# FiringBoard.net
KiCad netlist of a schematic drawn in Altium Designer
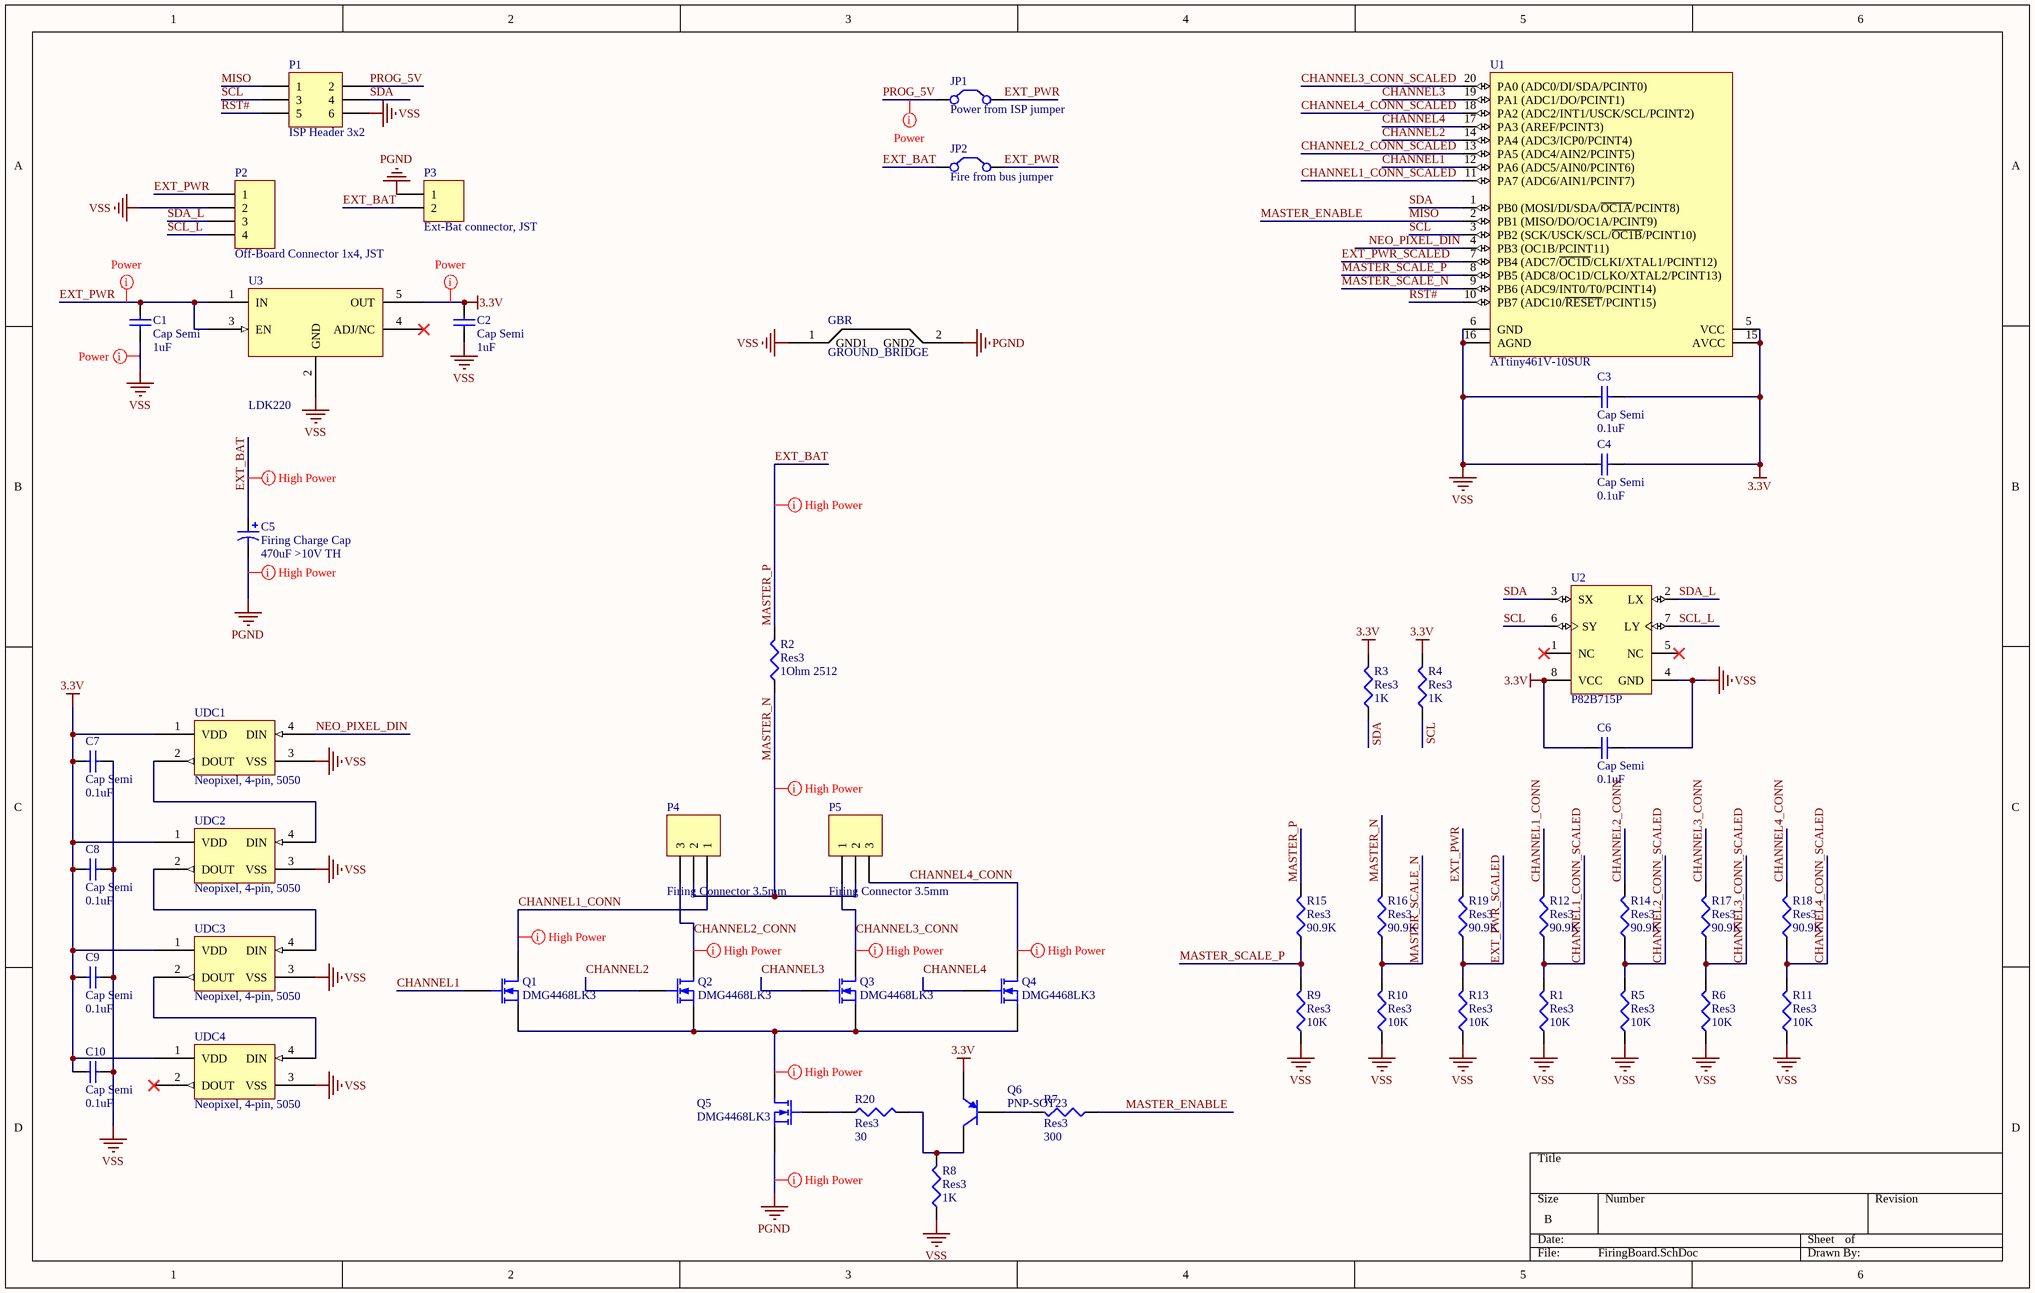
[diagram p0: FiringBoard.SchDoc]

(export (version "E")
  (design (tool "Eeschema 10.0.6"))
  (components
    (comp (ref "C1")
      (value "Cap Semi")
      (footprint "C0603")
      (description "Capacitor (Semiconductor SIM Model)")
      (fields (field (name "ALTIUM_VALUE") "1uF") (field (name "PUBLISHER") "Altium Limited"))
      (libsource (lib "Miscellaneous Devices") (part "Cap Semi"))
    )
    (comp (ref "C2")
      (value "Cap Semi")
      (footprint "C0603")
      (description "Capacitor (Semiconductor SIM Model)")
      (fields (field (name "ALTIUM_VALUE") "1uF") (field (name "PUBLISHER") "Altium Limited"))
      (libsource (lib "Miscellaneous Devices") (part "Cap Semi"))
    )
    (comp (ref "C3")
      (value "Cap Semi")
      (footprint "C0603")
      (description "Capacitor (Semiconductor SIM Model)")
      (fields (field (name "ALTIUM_VALUE") "0.1uF") (field (name "PUBLISHER") "Altium Limited"))
      (libsource (lib "Miscellaneous Devices") (part "Cap Semi"))
    )
    (comp (ref "C4")
      (value "Cap Semi")
      (footprint "C0603")
      (description "Capacitor (Semiconductor SIM Model)")
      (fields (field (name "ALTIUM_VALUE") "0.1uF") (field (name "PUBLISHER") "Altium Limited"))
      (libsource (lib "Miscellaneous Devices") (part "Cap Semi"))
    )
    (comp (ref "C5")
      (value "Firing Charge Cap")
      (footprint "CAPPR-10x12.5-Flat-Right")
      (description "Polarized Capacitor (Radial)")
      (fields (field (name "ALTIUM_VALUE") "470uF >10V TH") (field (name "PUBLISHER") "Altium Limited"))
      (libsource (lib "Miscellaneous Devices") (part "Cap Pol1"))
    )
    (comp (ref "C6")
      (value "Cap Semi")
      (footprint "C0603")
      (description "Capacitor (Semiconductor SIM Model)")
      (fields (field (name "ALTIUM_VALUE") "0.1uF") (field (name "PUBLISHER") "Altium Limited"))
      (libsource (lib "Miscellaneous Devices") (part "Cap Semi"))
    )
    (comp (ref "C7")
      (value "Cap Semi")
      (footprint "C0603")
      (description "Capacitor (Semiconductor SIM Model)")
      (fields (field (name "ALTIUM_VALUE") "0.1uF") (field (name "PUBLISHER") "Altium Limited"))
      (libsource (lib "Miscellaneous Devices") (part "Cap Semi"))
    )
    (comp (ref "C8")
      (value "Cap Semi")
      (footprint "C0603")
      (description "Capacitor (Semiconductor SIM Model)")
      (fields (field (name "ALTIUM_VALUE") "0.1uF") (field (name "PUBLISHER") "Altium Limited"))
      (libsource (lib "Miscellaneous Devices") (part "Cap Semi"))
    )
    (comp (ref "C9")
      (value "Cap Semi")
      (footprint "C0603")
      (description "Capacitor (Semiconductor SIM Model)")
      (fields (field (name "ALTIUM_VALUE") "0.1uF") (field (name "PUBLISHER") "Altium Limited"))
      (libsource (lib "Miscellaneous Devices") (part "Cap Semi"))
    )
    (comp (ref "C10")
      (value "Cap Semi")
      (footprint "C0603")
      (description "Capacitor (Semiconductor SIM Model)")
      (fields (field (name "ALTIUM_VALUE") "0.1uF") (field (name "PUBLISHER") "Altium Limited"))
      (libsource (lib "Miscellaneous Devices") (part "Cap Semi"))
    )
    (comp (ref "GBR")
      (value "GROUND_BRIDGE")
      (footprint "GROUND_BRIDGE")
      (libsource (lib "Schlib1") (part "GROUND_BRIDGE"))
    )
    (comp (ref "JP1")
      (value "Power from ISP jumper")
      (footprint "SOLDER-JUMPER-3D")
      (description "Solder Configuration Jumper")
      (fields (field (name "PUBLISHER") "Altium Limited"))
      (libsource (lib "SolarCar") (part "SolderJumper"))
    )
    (comp (ref "JP2")
      (value "Fire from bus jumper")
      (footprint "SOLDER-JUMPER-3D")
      (description "Solder Configuration Jumper")
      (fields (field (name "PUBLISHER") "Altium Limited"))
      (libsource (lib "SolarCar") (part "SolderJumper"))
    )
    (comp (ref "P1")
      (value "ISP Header 3x2")
      (footprint "HDR2X3-AVRISP")
      (description "Header, 3-Pin, Dual row")
      (fields (field (name "PUBLISHER") "Altium Limited"))
      (libsource (lib "Miscellaneous Connectors") (part "Header 3X2"))
    )
    (comp (ref "P2")
      (value "Off-Board Connector 1x4, JST")
      (footprint "1x04-1.5MM-JST")
      (description "Header, 4-Pin")
      (fields (field (name "PUBLISHER") "Altium Limited"))
      (libsource (lib "Miscellaneous Connectors") (part "Header 4"))
    )
    (comp (ref "P3")
      (value "Ext-Bat connector, JST")
      (footprint "JST-2-PTH-NS")
      (description "Header, 2-Pin")
      (fields (field (name "PUBLISHER") "Altium Limited"))
      (libsource (lib "Miscellaneous Connectors") (part "Header 2"))
    )
    (comp (ref "P4")
      (value "Firing Connector 3.5mm")
      (footprint "20020327-C031B01LF")
      (description "Header, 3-Pin")
      (fields (field (name "PUBLISHER") "Altium Limited"))
      (libsource (lib "") (part "Header 3_1"))
    )
    (comp (ref "P5")
      (value "Firing Connector 3.5mm")
      (footprint "20020327-C031B01LF")
      (description "Header, 3-Pin")
      (fields (field (name "PUBLISHER") "Altium Limited"))
      (libsource (lib "Miscellaneous Connectors") (part "Header 3"))
    )
    (comp (ref "Q1")
      (value "DMG4468LK3")
      (footprint "TO252")
      (description "N-CHANNEL ENHANCEMENT MODE MOSFET")
      (libsource (lib "Schlib1") (part "DMG4468LK3"))
    )
    (comp (ref "Q2")
      (value "DMG4468LK3")
      (footprint "TO252")
      (description "N-CHANNEL ENHANCEMENT MODE MOSFET")
      (libsource (lib "Schlib1") (part "DMG4468LK3"))
    )
    (comp (ref "Q3")
      (value "DMG4468LK3")
      (footprint "TO252")
      (description "N-CHANNEL ENHANCEMENT MODE MOSFET")
      (libsource (lib "Schlib1") (part "DMG4468LK3"))
    )
    (comp (ref "Q4")
      (value "DMG4468LK3")
      (footprint "TO252")
      (description "N-CHANNEL ENHANCEMENT MODE MOSFET")
      (libsource (lib "Schlib1") (part "DMG4468LK3"))
    )
    (comp (ref "Q5")
      (value "DMG4468LK3")
      (footprint "TO252")
      (description "N-CHANNEL ENHANCEMENT MODE MOSFET")
      (libsource (lib "Schlib1") (part "DMG4468LK3"))
    )
    (comp (ref "Q6")
      (value "PNP-SOT23")
      (footprint "SOT-23B_N")
      (description "PNP Bipolar Transistor - SOT23")
      (fields (field (name "PUBLISHER") "Altium Limited"))
      (libsource (lib "Schlib1") (part "PNP-SOT23"))
    )
    (comp (ref "R1")
      (value "Res3")
      (footprint "R0603-3D")
      (description "Resistor")
      (fields (field (name "ALTIUM_VALUE") "10K") (field (name "PUBLISHER") "Altium Limited"))
      (libsource (lib "Miscellaneous Devices") (part "Res3"))
    )
    (comp (ref "R2")
      (value "Res3")
      (footprint "R2512")
      (description "Resistor")
      (fields (field (name "ALTIUM_VALUE") "1Ohm 2512") (field (name "PUBLISHER") "Altium Limited"))
      (libsource (lib "Miscellaneous Devices") (part "Res3"))
    )
    (comp (ref "R3")
      (value "Res3")
      (footprint "R0603-3D")
      (description "Resistor")
      (fields (field (name "ALTIUM_VALUE") "1K") (field (name "PUBLISHER") "Altium Limited"))
      (libsource (lib "Miscellaneous Devices") (part "Res3"))
    )
    (comp (ref "R4")
      (value "Res3")
      (footprint "R0603-3D")
      (description "Resistor")
      (fields (field (name "ALTIUM_VALUE") "1K") (field (name "PUBLISHER") "Altium Limited"))
      (libsource (lib "Miscellaneous Devices") (part "Res3"))
    )
    (comp (ref "R5")
      (value "Res3")
      (footprint "R0603-3D")
      (description "Resistor")
      (fields (field (name "ALTIUM_VALUE") "10K") (field (name "PUBLISHER") "Altium Limited"))
      (libsource (lib "Miscellaneous Devices") (part "Res3"))
    )
    (comp (ref "R6")
      (value "Res3")
      (footprint "R0603-3D")
      (description "Resistor")
      (fields (field (name "ALTIUM_VALUE") "10K") (field (name "PUBLISHER") "Altium Limited"))
      (libsource (lib "Miscellaneous Devices") (part "Res3"))
    )
    (comp (ref "R7")
      (value "Res3")
      (footprint "R0603-3D")
      (description "Resistor")
      (fields (field (name "ALTIUM_VALUE") "300") (field (name "PUBLISHER") "Altium Limited"))
      (libsource (lib "Miscellaneous Devices") (part "Res3"))
    )
    (comp (ref "R8")
      (value "Res3")
      (footprint "R0603-3D")
      (description "Resistor")
      (fields (field (name "ALTIUM_VALUE") "1K") (field (name "PUBLISHER") "Altium Limited"))
      (libsource (lib "Miscellaneous Devices") (part "Res3"))
    )
    (comp (ref "R9")
      (value "Res3")
      (footprint "R0603-3D")
      (description "Resistor")
      (fields (field (name "ALTIUM_VALUE") "10K") (field (name "PUBLISHER") "Altium Limited"))
      (libsource (lib "Miscellaneous Devices") (part "Res3"))
    )
    (comp (ref "R10")
      (value "Res3")
      (footprint "R0603-3D")
      (description "Resistor")
      (fields (field (name "ALTIUM_VALUE") "10K") (field (name "PUBLISHER") "Altium Limited"))
      (libsource (lib "Miscellaneous Devices") (part "Res3"))
    )
    (comp (ref "R11")
      (value "Res3")
      (footprint "R0603-3D")
      (description "Resistor")
      (fields (field (name "ALTIUM_VALUE") "10K") (field (name "PUBLISHER") "Altium Limited"))
      (libsource (lib "Miscellaneous Devices") (part "Res3"))
    )
    (comp (ref "R12")
      (value "Res3")
      (footprint "R0603-3D")
      (description "Resistor")
      (fields (field (name "ALTIUM_VALUE") "90.9K") (field (name "PUBLISHER") "Altium Limited"))
      (libsource (lib "Miscellaneous Devices") (part "Res3"))
    )
    (comp (ref "R13")
      (value "Res3")
      (footprint "R0603-3D")
      (description "Resistor")
      (fields (field (name "ALTIUM_VALUE") "10K") (field (name "PUBLISHER") "Altium Limited"))
      (libsource (lib "Miscellaneous Devices") (part "Res3"))
    )
    (comp (ref "R14")
      (value "Res3")
      (footprint "R0603-3D")
      (description "Resistor")
      (fields (field (name "ALTIUM_VALUE") "90.9K") (field (name "PUBLISHER") "Altium Limited"))
      (libsource (lib "Miscellaneous Devices") (part "Res3"))
    )
    (comp (ref "R15")
      (value "Res3")
      (footprint "R0603-3D")
      (description "Resistor")
      (fields (field (name "ALTIUM_VALUE") "90.9K") (field (name "PUBLISHER") "Altium Limited"))
      (libsource (lib "Miscellaneous Devices") (part "Res3"))
    )
    (comp (ref "R16")
      (value "Res3")
      (footprint "R0603-3D")
      (description "Resistor")
      (fields (field (name "ALTIUM_VALUE") "90.9K") (field (name "PUBLISHER") "Altium Limited"))
      (libsource (lib "Miscellaneous Devices") (part "Res3"))
    )
    (comp (ref "R17")
      (value "Res3")
      (footprint "R0603-3D")
      (description "Resistor")
      (fields (field (name "ALTIUM_VALUE") "90.9K") (field (name "PUBLISHER") "Altium Limited"))
      (libsource (lib "Miscellaneous Devices") (part "Res3"))
    )
    (comp (ref "R18")
      (value "Res3")
      (footprint "R0603-3D")
      (description "Resistor")
      (fields (field (name "ALTIUM_VALUE") "90.9K") (field (name "PUBLISHER") "Altium Limited"))
      (libsource (lib "Miscellaneous Devices") (part "Res3"))
    )
    (comp (ref "R19")
      (value "Res3")
      (footprint "R0603-3D")
      (description "Resistor")
      (fields (field (name "ALTIUM_VALUE") "90.9K") (field (name "PUBLISHER") "Altium Limited"))
      (libsource (lib "Miscellaneous Devices") (part "Res3"))
    )
    (comp (ref "R20")
      (value "Res3")
      (footprint "R0603-3D")
      (description "Resistor")
      (fields (field (name "ALTIUM_VALUE") "30") (field (name "PUBLISHER") "Altium Limited"))
      (libsource (lib "Miscellaneous Devices") (part "Res3"))
    )
    (comp (ref "U1")
      (value "ATtiny461V-10SUR")
      (footprint "20S2_M")
      (libsource (lib "Altium Content Vault") (part "MC-8B-ATT261A-IL20"))
    )
    (comp (ref "U2")
      (value "P82B715P")
      (footprint "SO-G8")
      (description "I2C Bus Extender, 2 Channel Width, 3.0 to 12.0 V, -40 to 85 degC, 8-pin PDIP (P), Pb-Free (RoHS)")
      (fields (field (name "MANUFACTURER") "Texas Instruments"))
      (libsource (lib "Altium Content Vault") (part "TI-P82B715-PDIP_P-8"))
    )
    (comp (ref "U3")
      (value "LDK220")
      (footprint "SO-G5/P.95")
      (description "200 mA low quiescent current and low noise LDO")
      (libsource (lib "Schlib1") (part "LDK220"))
    )
    (comp (ref "UDC1")
      (value "Neopixel, 4-pin, 5050")
      (footprint "LED5050")
      (libsource (lib "Schlib1") (part "WS2812B"))
    )
    (comp (ref "UDC2")
      (value "Neopixel, 4-pin, 5050")
      (footprint "LED5050")
      (libsource (lib "Schlib1") (part "WS2812B"))
    )
    (comp (ref "UDC3")
      (value "Neopixel, 4-pin, 5050")
      (footprint "LED5050")
      (libsource (lib "Schlib1") (part "WS2812B"))
    )
    (comp (ref "UDC4")
      (value "Neopixel, 4-pin, 5050")
      (footprint "LED5050")
      (libsource (lib "Schlib1") (part "WS2812B"))
    )
  )
  (nets
    (net (code "1") (name "/CHANNEL1") (class "Default")
      (node (ref "Q1") (pin "1") (pinfunction "G_1") (pintype "passive"))
      (node (ref "U1") (pin "12") (pinfunction "PA6_(ADC5/AIN0/PCINT6)_12") (pintype "bidirectional"))
    )
    (net (code "2") (name "/CHANNEL1_CONN") (class "Default")
      (node (ref "P4") (pin "1") (pinfunction "1_1") (pintype "passive"))
      (node (ref "Q1") (pin "3") (pinfunction "D_3") (pintype "passive"))
      (node (ref "R12") (pin "2") (pinfunction "2_2") (pintype "passive"))
    )
    (net (code "3") (name "/CHANNEL1_CONN_SCALED") (class "Default")
      (node (ref "R1") (pin "2") (pinfunction "2_2") (pintype "passive"))
      (node (ref "R12") (pin "1") (pinfunction "1_1") (pintype "passive"))
      (node (ref "U1") (pin "11") (pinfunction "PA7_(ADC6/AIN1/PCINT7)_11") (pintype "bidirectional"))
    )
    (net (code "4") (name "/CHANNEL2") (class "Default")
      (node (ref "Q2") (pin "1") (pinfunction "G_1") (pintype "passive"))
      (node (ref "U1") (pin "14") (pinfunction "PA4_(ADC3/ICP0/PCINT4)_14") (pintype "bidirectional"))
    )
    (net (code "5") (name "/CHANNEL2_CONN") (class "Default")
      (node (ref "P4") (pin "3") (pinfunction "3_3") (pintype "passive"))
      (node (ref "Q2") (pin "3") (pinfunction "D_3") (pintype "passive"))
      (node (ref "R14") (pin "2") (pinfunction "2_2") (pintype "passive"))
    )
    (net (code "6") (name "/CHANNEL2_CONN_SCALED") (class "Default")
      (node (ref "R14") (pin "1") (pinfunction "1_1") (pintype "passive"))
      (node (ref "R5") (pin "2") (pinfunction "2_2") (pintype "passive"))
      (node (ref "U1") (pin "13") (pinfunction "PA5_(ADC4/AIN2/PCINT5)_13") (pintype "bidirectional"))
    )
    (net (code "7") (name "/CHANNEL3") (class "Default")
      (node (ref "Q3") (pin "1") (pinfunction "G_1") (pintype "passive"))
      (node (ref "U1") (pin "19") (pinfunction "PA1_(ADC1/DO/PCINT1)_19") (pintype "bidirectional"))
    )
    (net (code "8") (name "/CHANNEL3_CONN") (class "Default")
      (node (ref "P5") (pin "1") (pinfunction "1_1") (pintype "passive"))
      (node (ref "Q3") (pin "3") (pinfunction "D_3") (pintype "passive"))
      (node (ref "R17") (pin "2") (pinfunction "2_2") (pintype "passive"))
    )
    (net (code "9") (name "/CHANNEL3_CONN_SCALED") (class "Default")
      (node (ref "R17") (pin "1") (pinfunction "1_1") (pintype "passive"))
      (node (ref "R6") (pin "2") (pinfunction "2_2") (pintype "passive"))
      (node (ref "U1") (pin "20") (pinfunction "PA0_(ADC0/DI/SDA/PCINT0)_20") (pintype "bidirectional"))
    )
    (net (code "10") (name "/CHANNEL4") (class "Default")
      (node (ref "Q4") (pin "1") (pinfunction "G_1") (pintype "passive"))
      (node (ref "U1") (pin "17") (pinfunction "PA3_(AREF/PCINT3)_17") (pintype "bidirectional"))
    )
    (net (code "11") (name "/CHANNEL4_CONN") (class "Default")
      (node (ref "P5") (pin "3") (pinfunction "3_3") (pintype "passive"))
      (node (ref "Q4") (pin "3") (pinfunction "D_3") (pintype "passive"))
      (node (ref "R18") (pin "2") (pinfunction "2_2") (pintype "passive"))
    )
    (net (code "12") (name "/CHANNEL4_CONN_SCALED") (class "Default")
      (node (ref "R11") (pin "2") (pinfunction "2_2") (pintype "passive"))
      (node (ref "R18") (pin "1") (pinfunction "1_1") (pintype "passive"))
      (node (ref "U1") (pin "18") (pinfunction "PA2_(ADC2/INT1/USCK/SCL/PCINT2)_18") (pintype "bidirectional"))
    )
    (net (code "13") (name "/EXT_BAT") (class "Default")
      (node (ref "C5") (pin "1") (pinfunction "1_1") (pintype "passive"))
      (node (ref "JP2") (pin "1") (pinfunction "C1_1") (pintype "passive"))
      (node (ref "P3") (pin "2") (pinfunction "2_2") (pintype "passive"))
      (node (ref "R15") (pin "2") (pinfunction "2_2") (pintype "passive"))
      (node (ref "R2") (pin "2") (pinfunction "2_2") (pintype "passive"))
    )
    (net (code "14") (name "/EXT_PWR") (class "Default")
      (node (ref "C1") (pin "2") (pinfunction "2_2") (pintype "passive"))
      (node (ref "JP1") (pin "2") (pinfunction "C2_2") (pintype "passive"))
      (node (ref "JP2") (pin "2") (pinfunction "C2_2") (pintype "passive"))
      (node (ref "P2") (pin "1") (pinfunction "1_1") (pintype "passive"))
      (node (ref "R19") (pin "2") (pinfunction "2_2") (pintype "passive"))
      (node (ref "U3") (pin "1") (pinfunction "IN_1") (pintype "power_in"))
      (node (ref "U3") (pin "3") (pinfunction "EN_3") (pintype "input"))
    )
    (net (code "15") (name "/EXT_PWR_SCALED") (class "Default")
      (node (ref "R13") (pin "2") (pinfunction "2_2") (pintype "passive"))
      (node (ref "R19") (pin "1") (pinfunction "1_1") (pintype "passive"))
      (node (ref "U1") (pin "7") (pinfunction "PB4_(ADC7/~{OC1D}/CLKI/XTAL1/PCINT12)_7") (pintype "bidirectional"))
    )
    (net (code "16") (name "/MASTER_ENABLE") (class "Default")
      (node (ref "P1") (pin "1") (pinfunction "1_1") (pintype "passive"))
      (node (ref "R7") (pin "1") (pinfunction "1_1") (pintype "passive"))
      (node (ref "U1") (pin "2") (pinfunction "PB1_(MISO/DO/OC1A/PCINT9)_2") (pintype "bidirectional"))
    )
    (net (code "17") (name "/MASTER_N") (class "Default")
      (node (ref "P4") (pin "2") (pinfunction "2_2") (pintype "passive"))
      (node (ref "P5") (pin "2") (pinfunction "2_2") (pintype "passive"))
      (node (ref "R16") (pin "2") (pinfunction "2_2") (pintype "passive"))
      (node (ref "R2") (pin "1") (pinfunction "1_1") (pintype "passive"))
    )
    (net (code "18") (name "/MASTER_SCALE_N") (class "Default")
      (node (ref "R10") (pin "2") (pinfunction "2_2") (pintype "passive"))
      (node (ref "R16") (pin "1") (pinfunction "1_1") (pintype "passive"))
      (node (ref "U1") (pin "9") (pinfunction "PB6_(ADC9/INT0/T0/PCINT14)_9") (pintype "bidirectional"))
    )
    (net (code "19") (name "/MASTER_SCALE_P") (class "Default")
      (node (ref "R15") (pin "1") (pinfunction "1_1") (pintype "passive"))
      (node (ref "R9") (pin "2") (pinfunction "2_2") (pintype "passive"))
      (node (ref "U1") (pin "8") (pinfunction "PB5_(ADC8/OC1D/CLKO/XTAL2/PCINT13)_8") (pintype "bidirectional"))
    )
    (net (code "20") (name "/NEO_PIXEL_DIN") (class "Default")
      (node (ref "U1") (pin "4") (pinfunction "PB3_(OC1B/PCINT11)_4") (pintype "bidirectional"))
      (node (ref "UDC1") (pin "4") (pinfunction "DIN_4") (pintype "input"))
    )
    (net (code "21") (name "/PROG_5V") (class "Default")
      (node (ref "JP1") (pin "1") (pinfunction "C1_1") (pintype "passive"))
      (node (ref "P1") (pin "2") (pinfunction "2_2") (pintype "passive"))
    )
    (net (code "22") (name "/RST#") (class "Default")
      (node (ref "P1") (pin "5") (pinfunction "5_5") (pintype "passive"))
      (node (ref "U1") (pin "10") (pinfunction "PB7_(ADC10/~{RESET}/PCINT15)_10") (pintype "bidirectional"))
    )
    (net (code "23") (name "/SCL") (class "Default")
      (node (ref "P1") (pin "3") (pinfunction "3_3") (pintype "passive"))
      (node (ref "R4") (pin "1") (pinfunction "1_1") (pintype "passive"))
      (node (ref "U1") (pin "3") (pinfunction "PB2_(SCK/USCK/SCL/~{OC1B}/PCINT10)_3") (pintype "bidirectional"))
      (node (ref "U2") (pin "6") (pinfunction "SY_6") (pintype "bidirectional"))
    )
    (net (code "24") (name "/SCL_L") (class "Default")
      (node (ref "P2") (pin "4") (pinfunction "4_4") (pintype "passive"))
      (node (ref "U2") (pin "7") (pinfunction "LY_7") (pintype "bidirectional"))
    )
    (net (code "25") (name "/SDA") (class "Default")
      (node (ref "P1") (pin "4") (pinfunction "4_4") (pintype "passive"))
      (node (ref "R3") (pin "1") (pinfunction "1_1") (pintype "passive"))
      (node (ref "U1") (pin "1") (pinfunction "PB0_(MOSI/DI/SDA/~{OC1A}/PCINT8)_1") (pintype "bidirectional"))
      (node (ref "U2") (pin "3") (pinfunction "SX_3") (pintype "bidirectional"))
    )
    (net (code "26") (name "/SDA_L") (class "Default")
      (node (ref "P2") (pin "3") (pinfunction "3_3") (pintype "passive"))
      (node (ref "U2") (pin "2") (pinfunction "LX_2") (pintype "bidirectional"))
    )
    (net (code "27") (name "3.3V") (class "Default")
      (node (ref "C10") (pin "2") (pinfunction "2_2") (pintype "passive"))
      (node (ref "C2") (pin "2") (pinfunction "2_2") (pintype "passive"))
      (node (ref "C3") (pin "2") (pinfunction "2_2") (pintype "passive"))
      (node (ref "C4") (pin "2") (pinfunction "2_2") (pintype "passive"))
      (node (ref "C6") (pin "1") (pinfunction "1_1") (pintype "passive"))
      (node (ref "C7") (pin "2") (pinfunction "2_2") (pintype "passive"))
      (node (ref "C8") (pin "2") (pinfunction "2_2") (pintype "passive"))
      (node (ref "C9") (pin "2") (pinfunction "2_2") (pintype "passive"))
      (node (ref "Q6") (pin "2") (pinfunction "E_2") (pintype "passive"))
      (node (ref "R3") (pin "2") (pinfunction "2_2") (pintype "passive"))
      (node (ref "R4") (pin "2") (pinfunction "2_2") (pintype "passive"))
      (node (ref "U1") (pin "15") (pinfunction "AVCC_15") (pintype "power_in"))
      (node (ref "U1") (pin "5") (pinfunction "VCC_5") (pintype "power_in"))
      (node (ref "U2") (pin "8") (pinfunction "VCC_8") (pintype "power_in"))
      (node (ref "U3") (pin "5") (pinfunction "OUT_5") (pintype "power_in"))
      (node (ref "UDC1") (pin "1") (pinfunction "VDD_1") (pintype "power_in"))
      (node (ref "UDC2") (pin "1") (pinfunction "VDD_1") (pintype "power_in"))
      (node (ref "UDC3") (pin "1") (pinfunction "VDD_1") (pintype "power_in"))
      (node (ref "UDC4") (pin "1") (pinfunction "VDD_1") (pintype "power_in"))
    )
    (net (code "28") (name "Net-(Q1-S)") (class "Default")
      (node (ref "Q1") (pin "2") (pinfunction "S_2") (pintype "passive"))
      (node (ref "Q2") (pin "2") (pinfunction "S_2") (pintype "passive"))
      (node (ref "Q3") (pin "2") (pinfunction "S_2") (pintype "passive"))
      (node (ref "Q4") (pin "2") (pinfunction "S_2") (pintype "passive"))
      (node (ref "Q5") (pin "3") (pinfunction "D_3") (pintype "passive"))
    )
    (net (code "29") (name "Net-(Q5-G)") (class "Default")
      (node (ref "Q5") (pin "1") (pinfunction "G_1") (pintype "passive"))
      (node (ref "R20") (pin "1") (pinfunction "1_1") (pintype "passive"))
    )
    (net (code "30") (name "Net-(Q6-B)") (class "Default")
      (node (ref "Q6") (pin "1") (pinfunction "B_1") (pintype "passive"))
      (node (ref "R7") (pin "2") (pinfunction "2_2") (pintype "passive"))
    )
    (net (code "31") (name "Net-(Q6-C)") (class "Default")
      (node (ref "Q6") (pin "3") (pinfunction "C_3") (pintype "passive"))
      (node (ref "R20") (pin "2") (pinfunction "2_2") (pintype "passive"))
      (node (ref "R8") (pin "2") (pinfunction "2_2") (pintype "passive"))
    )
    (net (code "32") (name "Net-(UDC1-DOUT)") (class "Default")
      (node (ref "UDC1") (pin "2") (pinfunction "DOUT_2") (pintype "output"))
      (node (ref "UDC2") (pin "4") (pinfunction "DIN_4") (pintype "input"))
    )
    (net (code "33") (name "Net-(UDC2-DOUT)") (class "Default")
      (node (ref "UDC2") (pin "2") (pinfunction "DOUT_2") (pintype "output"))
      (node (ref "UDC3") (pin "4") (pinfunction "DIN_4") (pintype "input"))
    )
    (net (code "34") (name "Net-(UDC3-DOUT)") (class "Default")
      (node (ref "UDC3") (pin "2") (pinfunction "DOUT_2") (pintype "output"))
      (node (ref "UDC4") (pin "4") (pinfunction "DIN_4") (pintype "input"))
    )
    (net (code "35") (name "PGND") (class "Default")
      (node (ref "C5") (pin "2") (pinfunction "2_2") (pintype "passive"))
      (node (ref "GBR") (pin "2") (pinfunction "GND2_2") (pintype "power_in"))
      (node (ref "P3") (pin "1") (pinfunction "1_1") (pintype "passive"))
      (node (ref "Q5") (pin "2") (pinfunction "S_2") (pintype "passive"))
    )
    (net (code "36") (name "VSS") (class "Default")
      (node (ref "C1") (pin "1") (pinfunction "1_1") (pintype "passive"))
      (node (ref "C10") (pin "1") (pinfunction "1_1") (pintype "passive"))
      (node (ref "C2") (pin "1") (pinfunction "1_1") (pintype "passive"))
      (node (ref "C3") (pin "1") (pinfunction "1_1") (pintype "passive"))
      (node (ref "C4") (pin "1") (pinfunction "1_1") (pintype "passive"))
      (node (ref "C6") (pin "2") (pinfunction "2_2") (pintype "passive"))
      (node (ref "C7") (pin "1") (pinfunction "1_1") (pintype "passive"))
      (node (ref "C8") (pin "1") (pinfunction "1_1") (pintype "passive"))
      (node (ref "C9") (pin "1") (pinfunction "1_1") (pintype "passive"))
      (node (ref "GBR") (pin "1") (pinfunction "GND1_1") (pintype "power_in"))
      (node (ref "P1") (pin "6") (pinfunction "6_6") (pintype "passive"))
      (node (ref "P2") (pin "2") (pinfunction "2_2") (pintype "passive"))
      (node (ref "R1") (pin "1") (pinfunction "1_1") (pintype "passive"))
      (node (ref "R10") (pin "1") (pinfunction "1_1") (pintype "passive"))
      (node (ref "R11") (pin "1") (pinfunction "1_1") (pintype "passive"))
      (node (ref "R13") (pin "1") (pinfunction "1_1") (pintype "passive"))
      (node (ref "R5") (pin "1") (pinfunction "1_1") (pintype "passive"))
      (node (ref "R6") (pin "1") (pinfunction "1_1") (pintype "passive"))
      (node (ref "R8") (pin "1") (pinfunction "1_1") (pintype "passive"))
      (node (ref "R9") (pin "1") (pinfunction "1_1") (pintype "passive"))
      (node (ref "U1") (pin "16") (pinfunction "AGND_16") (pintype "power_in"))
      (node (ref "U1") (pin "6") (pinfunction "GND_6") (pintype "power_in"))
      (node (ref "U2") (pin "4") (pinfunction "GND_4") (pintype "power_in"))
      (node (ref "U3") (pin "2") (pinfunction "GND_2") (pintype "power_in"))
      (node (ref "UDC1") (pin "3") (pinfunction "VSS_3") (pintype "power_in"))
      (node (ref "UDC2") (pin "3") (pinfunction "VSS_3") (pintype "power_in"))
      (node (ref "UDC3") (pin "3") (pinfunction "VSS_3") (pintype "power_in"))
      (node (ref "UDC4") (pin "3") (pinfunction "VSS_3") (pintype "power_in"))
    )
    (net (code "37") (name "unconnected-(U2-NC-Pad1)") (class "Default")
      (node (ref "U2") (pin "1") (pinfunction "NC_1") (pintype "passive+no_connect"))
    )
    (net (code "38") (name "unconnected-(U2-NC-Pad5)") (class "Default")
      (node (ref "U2") (pin "5") (pinfunction "NC_5") (pintype "passive+no_connect"))
    )
    (net (code "39") (name "unconnected-(U3-ADJ{slash}NC-Pad4)") (class "Default")
      (node (ref "U3") (pin "4") (pinfunction "ADJ/NC_4") (pintype "passive+no_connect"))
    )
    (net (code "40") (name "unconnected-(UDC4-DOUT-Pad2)") (class "Default")
      (node (ref "UDC4") (pin "2") (pinfunction "DOUT_2") (pintype "output+no_connect"))
    )
  )
)
